# Controller-Sheet.net
KiCad netlist of a schematic drawn in Altium Designer
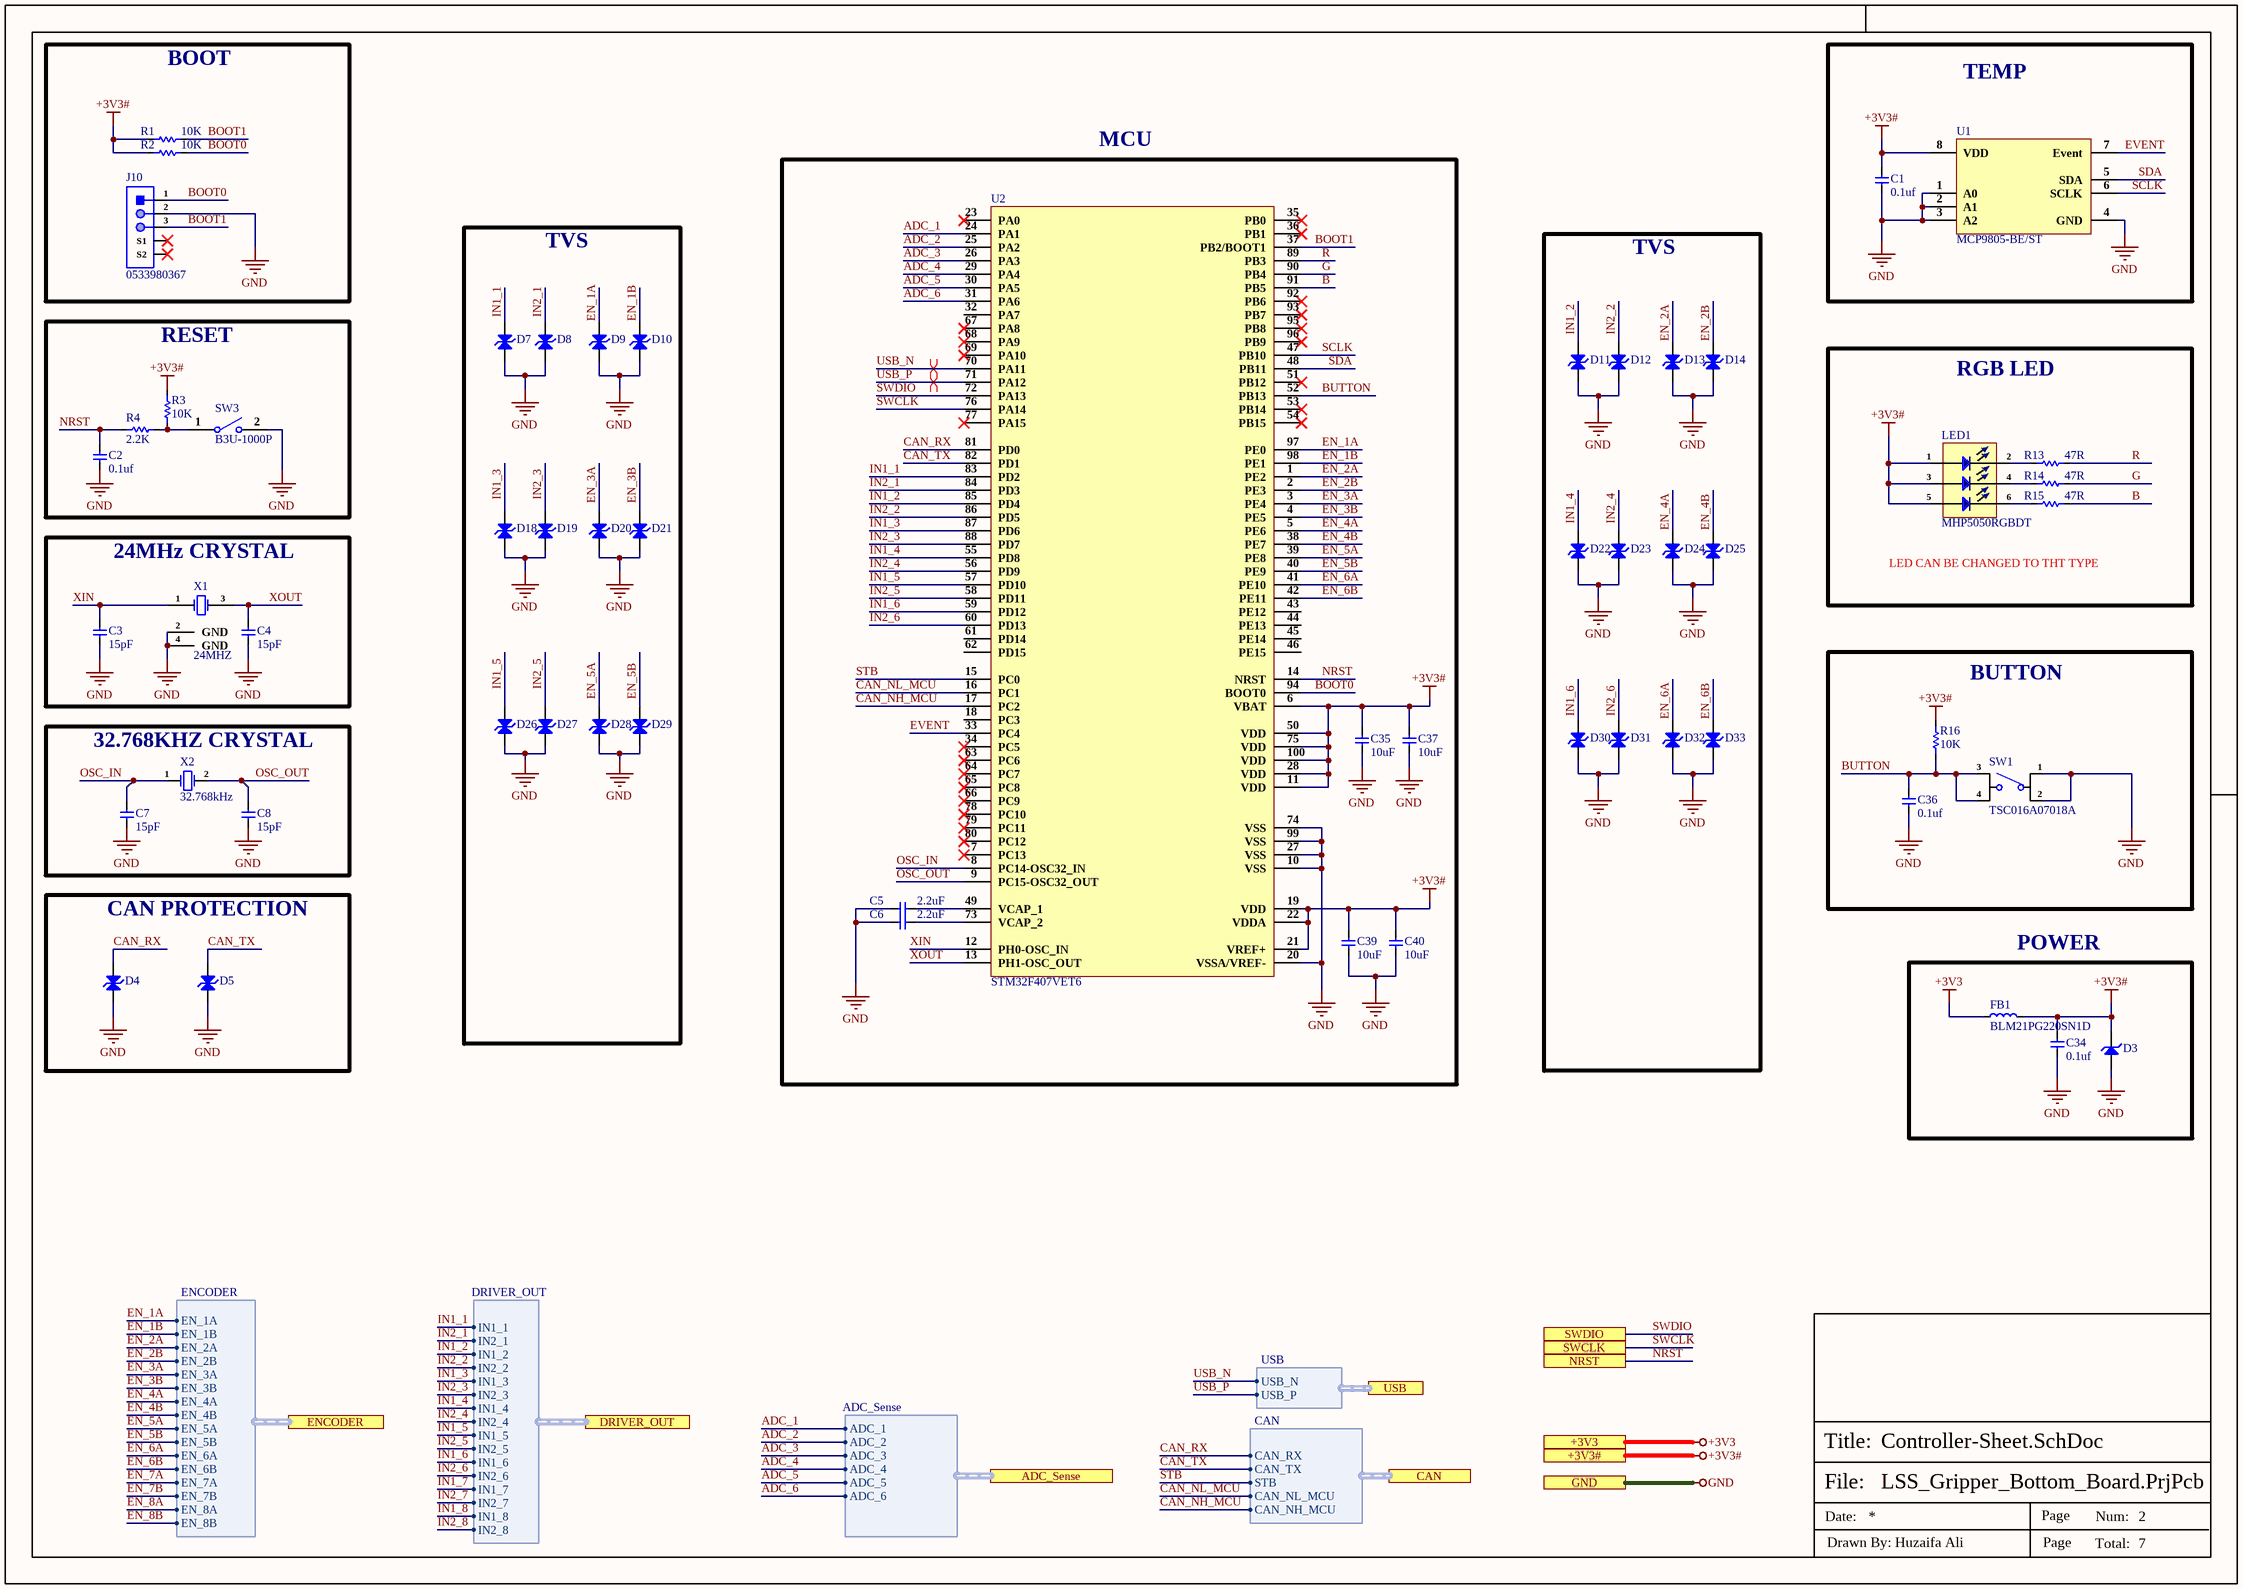
[diagram p0: Controller-Sheet.SchDoc]

(export (version "E")
  (design (tool "Eeschema 10.0.6"))
  (components
    (comp (ref "C1")
      (value "0.1uf")
      (footprint "Cap-0402")
      (description "CAP CER 0.1UF 100V X5R 0402")
      (fields
        (field (name "MANUFACTURER") "Murata")
        (field (name "MANUFACTURER PART NUMBER") "GRM155R62A104KE14D")
      )
      (libsource (lib "eSpark Libraries") (part "GRM155R62A104KE14D"))
    )
    (comp (ref "C2")
      (value "0.1uf")
      (footprint "Cap-0402")
      (description "CAP CER 0.1UF 100V X5R 0402")
      (fields
        (field (name "MANUFACTURER") "Murata")
        (field (name "MANUFACTURER PART NUMBER") "GRM155R62A104KE14D")
      )
      (libsource (lib "eSpark Libraries") (part "GRM155R62A104KE14D"))
    )
    (comp (ref "C3")
      (value "15pF")
      (footprint "Cap-0201")
      (description "CAP CER 15PF 50V C0G/NPO 0201")
      (fields
        (field (name "MANUFACTURER") "Yageo")
        (field (name "MANUFACTURER PART NUMBER") "CC0201JRNPO9BN150")
      )
      (libsource (lib "eSpark Libraries") (part "CC0201JRNPO9BN150"))
    )
    (comp (ref "C4")
      (value "15pF")
      (footprint "Cap-0201")
      (description "CAP CER 15PF 50V C0G/NPO 0201")
      (fields
        (field (name "MANUFACTURER") "Yageo")
        (field (name "MANUFACTURER PART NUMBER") "CC0201JRNPO9BN150")
      )
      (libsource (lib "eSpark Libraries") (part "CC0201JRNPO9BN150"))
    )
    (comp (ref "C5")
      (value "2.2uF")
      (footprint "Cap-0402")
      (description "CAP CER 2.2UF 6.3V X5R 0402")
      (fields
        (field (name "LCSC PART NUMBER") "C343036")
        (field (name "MANUFACTURER PART NUMBER") "C1005X5R0J225KTJA0E")
      )
      (libsource (lib "eSpark Libraries") (part "C1005X5R0J225KTJA0E"))
    )
    (comp (ref "C6")
      (value "2.2uF")
      (footprint "Cap-0402")
      (description "CAP CER 2.2UF 6.3V X5R 0402")
      (fields
        (field (name "LCSC PART NUMBER") "C343036")
        (field (name "MANUFACTURER PART NUMBER") "C1005X5R0J225KTJA0E")
      )
      (libsource (lib "eSpark Libraries") (part "C1005X5R0J225KTJA0E"))
    )
    (comp (ref "C7")
      (value "15pF")
      (footprint "Cap-0201")
      (description "CAP CER 15PF 50V C0G/NPO 0201")
      (fields
        (field (name "MANUFACTURER") "Yageo")
        (field (name "MANUFACTURER PART NUMBER") "CC0201JRNPO9BN150")
      )
      (libsource (lib "eSpark Libraries") (part "CC0201JRNPO9BN150"))
    )
    (comp (ref "C8")
      (value "15pF")
      (footprint "Cap-0201")
      (description "CAP CER 15PF 50V C0G/NPO 0201")
      (fields
        (field (name "MANUFACTURER") "Yageo")
        (field (name "MANUFACTURER PART NUMBER") "CC0201JRNPO9BN150")
      )
      (libsource (lib "eSpark Libraries") (part "CC0201JRNPO9BN150"))
    )
    (comp (ref "C34")
      (value "0.1uf")
      (footprint "Cap-0402")
      (description "CAP CER 0.1UF 100V X5R 0402")
      (fields
        (field (name "MANUFACTURER") "Murata")
        (field (name "MANUFACTURER PART NUMBER") "GRM155R62A104KE14D")
      )
      (libsource (lib "eSpark Libraries") (part "GRM155R62A104KE14D"))
    )
    (comp (ref "C35")
      (value "10uF")
      (footprint "Cap-0402")
      (description "CAP CER 10UF 10V X5R 0402")
      (fields
        (field (name "MANUFACTURER") "Samsung")
        (field (name "MANUFACTURER PART NUMBER") "CL05A106MP5NUNC")
      )
      (libsource (lib "eSpark Libraries") (part "CL05A106MP5NUNC"))
    )
    (comp (ref "C36")
      (value "0.1uf")
      (footprint "Cap-0402")
      (description "CAP CER 0.1UF 100V X5R 0402")
      (fields
        (field (name "MANUFACTURER") "Murata")
        (field (name "MANUFACTURER PART NUMBER") "GRM155R62A104KE14D")
      )
      (libsource (lib "eSpark Libraries") (part "GRM155R62A104KE14D"))
    )
    (comp (ref "C37")
      (value "10uF")
      (footprint "Cap-0402")
      (description "CAP CER 10UF 10V X5R 0402")
      (fields
        (field (name "MANUFACTURER") "Samsung")
        (field (name "MANUFACTURER PART NUMBER") "CL05A106MP5NUNC")
      )
      (libsource (lib "eSpark Libraries") (part "CL05A106MP5NUNC"))
    )
    (comp (ref "C39")
      (value "10uF")
      (footprint "Cap-0402")
      (description "CAP CER 10UF 10V X5R 0402")
      (fields
        (field (name "MANUFACTURER") "Samsung")
        (field (name "MANUFACTURER PART NUMBER") "CL05A106MP5NUNC")
      )
      (libsource (lib "eSpark Libraries") (part "CL05A106MP5NUNC"))
    )
    (comp (ref "C40")
      (value "10uF")
      (footprint "Cap-0402")
      (description "CAP CER 10UF 10V X5R 0402")
      (fields
        (field (name "MANUFACTURER") "Samsung")
        (field (name "MANUFACTURER PART NUMBER") "CL05A106MP5NUNC")
      )
      (libsource (lib "eSpark Libraries") (part "CL05A106MP5NUNC"))
    )
    (comp (ref "D3")
      (value "AZ3003-01G")
      (footprint "SOD-123")
      (description "TVS SURGE PROTECTOR 1-CH 3.3V")
      (fields (field (name "MANUFACTURER") "Amazing"))
      (libsource (lib "eSpark Libraries") (part "AZ3003-01G"))
    )
    (comp (ref "D4")
      (value "PESD3V3Y1BSFYL")
      (footprint "DSN0603-2")
      (description "TVS DIODE 3.3VWM 3.7VC DSN0603-2")
      (fields (field (name "MANUFACTURER") "Nexperia") (field (name "LCSC PART NUMBER") "C552535"))
      (libsource (lib "eSpark Libraries") (part "PESD3V3Y1BSFYL"))
    )
    (comp (ref "D5")
      (value "PESD3V3Y1BSFYL")
      (footprint "DSN0603-2")
      (description "TVS DIODE 3.3VWM 3.7VC DSN0603-2")
      (fields (field (name "MANUFACTURER") "Nexperia") (field (name "LCSC PART NUMBER") "C552535"))
      (libsource (lib "eSpark Libraries") (part "PESD3V3Y1BSFYL"))
    )
    (comp (ref "D7")
      (value "PESD3V3Y1BSFYL")
      (footprint "DSN0603-2")
      (description "TVS DIODE 3.3VWM 3.7VC DSN0603-2")
      (fields (field (name "MANUFACTURER") "Nexperia") (field (name "LCSC PART NUMBER") "C552535"))
      (libsource (lib "eSpark Libraries") (part "PESD3V3Y1BSFYL"))
    )
    (comp (ref "D8")
      (value "PESD3V3Y1BSFYL")
      (footprint "DSN0603-2")
      (description "TVS DIODE 3.3VWM 3.7VC DSN0603-2")
      (fields (field (name "MANUFACTURER") "Nexperia") (field (name "LCSC PART NUMBER") "C552535"))
      (libsource (lib "eSpark Libraries") (part "PESD3V3Y1BSFYL"))
    )
    (comp (ref "D9")
      (value "PESD3V3Y1BSFYL")
      (footprint "DSN0603-2")
      (description "TVS DIODE 3.3VWM 3.7VC DSN0603-2")
      (fields (field (name "MANUFACTURER") "Nexperia") (field (name "LCSC PART NUMBER") "C552535"))
      (libsource (lib "eSpark Libraries") (part "PESD3V3Y1BSFYL"))
    )
    (comp (ref "D10")
      (value "PESD3V3Y1BSFYL")
      (footprint "DSN0603-2")
      (description "TVS DIODE 3.3VWM 3.7VC DSN0603-2")
      (fields (field (name "MANUFACTURER") "Nexperia") (field (name "LCSC PART NUMBER") "C552535"))
      (libsource (lib "eSpark Libraries") (part "PESD3V3Y1BSFYL"))
    )
    (comp (ref "D11")
      (value "PESD3V3Y1BSFYL")
      (footprint "DSN0603-2")
      (description "TVS DIODE 3.3VWM 3.7VC DSN0603-2")
      (fields (field (name "MANUFACTURER") "Nexperia") (field (name "LCSC PART NUMBER") "C552535"))
      (libsource (lib "eSpark Libraries") (part "PESD3V3Y1BSFYL"))
    )
    (comp (ref "D12")
      (value "PESD3V3Y1BSFYL")
      (footprint "DSN0603-2")
      (description "TVS DIODE 3.3VWM 3.7VC DSN0603-2")
      (fields (field (name "MANUFACTURER") "Nexperia") (field (name "LCSC PART NUMBER") "C552535"))
      (libsource (lib "eSpark Libraries") (part "PESD3V3Y1BSFYL"))
    )
    (comp (ref "D13")
      (value "PESD3V3Y1BSFYL")
      (footprint "DSN0603-2")
      (description "TVS DIODE 3.3VWM 3.7VC DSN0603-2")
      (fields (field (name "MANUFACTURER") "Nexperia") (field (name "LCSC PART NUMBER") "C552535"))
      (libsource (lib "eSpark Libraries") (part "PESD3V3Y1BSFYL"))
    )
    (comp (ref "D14")
      (value "PESD3V3Y1BSFYL")
      (footprint "DSN0603-2")
      (description "TVS DIODE 3.3VWM 3.7VC DSN0603-2")
      (fields (field (name "MANUFACTURER") "Nexperia") (field (name "LCSC PART NUMBER") "C552535"))
      (libsource (lib "eSpark Libraries") (part "PESD3V3Y1BSFYL"))
    )
    (comp (ref "D18")
      (value "PESD3V3Y1BSFYL")
      (footprint "DSN0603-2")
      (description "TVS DIODE 3.3VWM 3.7VC DSN0603-2")
      (fields (field (name "MANUFACTURER") "Nexperia") (field (name "LCSC PART NUMBER") "C552535"))
      (libsource (lib "eSpark Libraries") (part "PESD3V3Y1BSFYL"))
    )
    (comp (ref "D19")
      (value "PESD3V3Y1BSFYL")
      (footprint "DSN0603-2")
      (description "TVS DIODE 3.3VWM 3.7VC DSN0603-2")
      (fields (field (name "MANUFACTURER") "Nexperia") (field (name "LCSC PART NUMBER") "C552535"))
      (libsource (lib "eSpark Libraries") (part "PESD3V3Y1BSFYL"))
    )
    (comp (ref "D20")
      (value "PESD3V3Y1BSFYL")
      (footprint "DSN0603-2")
      (description "TVS DIODE 3.3VWM 3.7VC DSN0603-2")
      (fields (field (name "MANUFACTURER") "Nexperia") (field (name "LCSC PART NUMBER") "C552535"))
      (libsource (lib "eSpark Libraries") (part "PESD3V3Y1BSFYL"))
    )
    (comp (ref "D21")
      (value "PESD3V3Y1BSFYL")
      (footprint "DSN0603-2")
      (description "TVS DIODE 3.3VWM 3.7VC DSN0603-2")
      (fields (field (name "MANUFACTURER") "Nexperia") (field (name "LCSC PART NUMBER") "C552535"))
      (libsource (lib "eSpark Libraries") (part "PESD3V3Y1BSFYL"))
    )
    (comp (ref "D22")
      (value "PESD3V3Y1BSFYL")
      (footprint "DSN0603-2")
      (description "TVS DIODE 3.3VWM 3.7VC DSN0603-2")
      (fields (field (name "MANUFACTURER") "Nexperia") (field (name "LCSC PART NUMBER") "C552535"))
      (libsource (lib "eSpark Libraries") (part "PESD3V3Y1BSFYL"))
    )
    (comp (ref "D23")
      (value "PESD3V3Y1BSFYL")
      (footprint "DSN0603-2")
      (description "TVS DIODE 3.3VWM 3.7VC DSN0603-2")
      (fields (field (name "MANUFACTURER") "Nexperia") (field (name "LCSC PART NUMBER") "C552535"))
      (libsource (lib "eSpark Libraries") (part "PESD3V3Y1BSFYL"))
    )
    (comp (ref "D24")
      (value "PESD3V3Y1BSFYL")
      (footprint "DSN0603-2")
      (description "TVS DIODE 3.3VWM 3.7VC DSN0603-2")
      (fields (field (name "MANUFACTURER") "Nexperia") (field (name "LCSC PART NUMBER") "C552535"))
      (libsource (lib "eSpark Libraries") (part "PESD3V3Y1BSFYL"))
    )
    (comp (ref "D25")
      (value "PESD3V3Y1BSFYL")
      (footprint "DSN0603-2")
      (description "TVS DIODE 3.3VWM 3.7VC DSN0603-2")
      (fields (field (name "MANUFACTURER") "Nexperia") (field (name "LCSC PART NUMBER") "C552535"))
      (libsource (lib "eSpark Libraries") (part "PESD3V3Y1BSFYL"))
    )
    (comp (ref "D26")
      (value "PESD3V3Y1BSFYL")
      (footprint "DSN0603-2")
      (description "TVS DIODE 3.3VWM 3.7VC DSN0603-2")
      (fields (field (name "MANUFACTURER") "Nexperia") (field (name "LCSC PART NUMBER") "C552535"))
      (libsource (lib "eSpark Libraries") (part "PESD3V3Y1BSFYL"))
    )
    (comp (ref "D27")
      (value "PESD3V3Y1BSFYL")
      (footprint "DSN0603-2")
      (description "TVS DIODE 3.3VWM 3.7VC DSN0603-2")
      (fields (field (name "MANUFACTURER") "Nexperia") (field (name "LCSC PART NUMBER") "C552535"))
      (libsource (lib "eSpark Libraries") (part "PESD3V3Y1BSFYL"))
    )
    (comp (ref "D28")
      (value "PESD3V3Y1BSFYL")
      (footprint "DSN0603-2")
      (description "TVS DIODE 3.3VWM 3.7VC DSN0603-2")
      (fields (field (name "MANUFACTURER") "Nexperia") (field (name "LCSC PART NUMBER") "C552535"))
      (libsource (lib "eSpark Libraries") (part "PESD3V3Y1BSFYL"))
    )
    (comp (ref "D29")
      (value "PESD3V3Y1BSFYL")
      (footprint "DSN0603-2")
      (description "TVS DIODE 3.3VWM 3.7VC DSN0603-2")
      (fields (field (name "MANUFACTURER") "Nexperia") (field (name "LCSC PART NUMBER") "C552535"))
      (libsource (lib "eSpark Libraries") (part "PESD3V3Y1BSFYL"))
    )
    (comp (ref "D30")
      (value "PESD3V3Y1BSFYL")
      (footprint "DSN0603-2")
      (description "TVS DIODE 3.3VWM 3.7VC DSN0603-2")
      (fields (field (name "MANUFACTURER") "Nexperia") (field (name "LCSC PART NUMBER") "C552535"))
      (libsource (lib "eSpark Libraries") (part "PESD3V3Y1BSFYL"))
    )
    (comp (ref "D31")
      (value "PESD3V3Y1BSFYL")
      (footprint "DSN0603-2")
      (description "TVS DIODE 3.3VWM 3.7VC DSN0603-2")
      (fields (field (name "MANUFACTURER") "Nexperia") (field (name "LCSC PART NUMBER") "C552535"))
      (libsource (lib "eSpark Libraries") (part "PESD3V3Y1BSFYL"))
    )
    (comp (ref "D32")
      (value "PESD3V3Y1BSFYL")
      (footprint "DSN0603-2")
      (description "TVS DIODE 3.3VWM 3.7VC DSN0603-2")
      (fields (field (name "MANUFACTURER") "Nexperia") (field (name "LCSC PART NUMBER") "C552535"))
      (libsource (lib "eSpark Libraries") (part "PESD3V3Y1BSFYL"))
    )
    (comp (ref "D33")
      (value "PESD3V3Y1BSFYL")
      (footprint "DSN0603-2")
      (description "TVS DIODE 3.3VWM 3.7VC DSN0603-2")
      (fields (field (name "MANUFACTURER") "Nexperia") (field (name "LCSC PART NUMBER") "C552535"))
      (libsource (lib "eSpark Libraries") (part "PESD3V3Y1BSFYL"))
    )
    (comp (ref "FB1")
      (value "BLM21PG220SN1D")
      (footprint "Ind-0805")
      (description "FERRITE BEAD 22 OHM 0805 1LN")
      (fields (field (name "MANUFACTURER") "Murata") (field (name "LCSC PART NUMBER") "C88993"))
      (libsource (lib "eSpark Libraries") (part "BLM21PG220SN1D"))
    )
    (comp (ref "J10")
      (value "0533980367")
      (footprint "0533980367")
      (description "CONN HEADER SMD 3POS 1.25MM")
      (fields (field (name "MANUFACTURER") "Molex") (field (name "LCSC PART NUMBER") "C17555262"))
      (libsource (lib "eSpark Libraries") (part "0533980367"))
    )
    (comp (ref "LED1")
      (value "MHP5050RGBDT")
      (footprint "SMD5050")
      (description "20mA White Diffused -40℃~+85℃ RGB SMD5050 Light Emitting Diodes (LED) ROHS")
      (fields (field (name "MANUFACTURER") "MEIHUA") (field (name "LCSC PART NUMBER") "C409780"))
      (libsource (lib "eSpark Libraries") (part "MHP5050RGBDT"))
    )
    (comp (ref "R1")
      (value "10K")
      (footprint "Res-0402")
      (description "RES 10K OHM 1% 1/16W 0402")
      (fields
        (field (name "MANUFACTURER") "Yageo")
        (field (name "MANUFACTURER PART NUMBER") "RC0402FR-0710KL")
      )
      (libsource (lib "eSpark Libraries") (part "RC0402FR-0710KL"))
    )
    (comp (ref "R2")
      (value "10K")
      (footprint "Res-0402")
      (description "RES 10K OHM 1% 1/16W 0402")
      (fields
        (field (name "MANUFACTURER") "Yageo")
        (field (name "MANUFACTURER PART NUMBER") "RC0402FR-0710KL")
      )
      (libsource (lib "eSpark Libraries") (part "RC0402FR-0710KL"))
    )
    (comp (ref "R3")
      (value "10K")
      (footprint "Res-0402")
      (description "RES 10K OHM 1% 1/16W 0402")
      (fields
        (field (name "MANUFACTURER") "Yageo")
        (field (name "MANUFACTURER PART NUMBER") "RC0402FR-0710KL")
      )
      (libsource (lib "eSpark Libraries") (part "RC0402FR-0710KL"))
    )
    (comp (ref "R4")
      (value "2.2K")
      (footprint "Res-0603")
      (description "RES SMD 2.2K OHM 0.1% 1/10W 0603")
      (fields
        (field (name "MANUFACTURER") "Yageo")
        (field (name "MANUFACTURER PART NUMBER") "RT0603BRB072K2L")
      )
      (libsource (lib "eSpark Libraries") (part "RT0603BRB072K2L"))
    )
    (comp (ref "R13")
      (value "47R")
      (footprint "Res-0402")
      (description "RES 47 OHM 1% 1/16W 0402")
      (fields
        (field (name "MANUFACTURER") "Yageo")
        (field (name "MANUFACTURER PART NUMBER") "RC0402FR-0747RL")
      )
      (libsource (lib "eSpark Libraries") (part "RC0402FR-0747RL"))
    )
    (comp (ref "R14")
      (value "47R")
      (footprint "Res-0402")
      (description "RES 47 OHM 1% 1/16W 0402")
      (fields
        (field (name "MANUFACTURER") "Yageo")
        (field (name "MANUFACTURER PART NUMBER") "RC0402FR-0747RL")
      )
      (libsource (lib "eSpark Libraries") (part "RC0402FR-0747RL"))
    )
    (comp (ref "R15")
      (value "47R")
      (footprint "Res-0402")
      (description "RES 47 OHM 1% 1/16W 0402")
      (fields
        (field (name "MANUFACTURER") "Yageo")
        (field (name "MANUFACTURER PART NUMBER") "RC0402FR-0747RL")
      )
      (libsource (lib "eSpark Libraries") (part "RC0402FR-0747RL"))
    )
    (comp (ref "R16")
      (value "10K")
      (footprint "Res-0402")
      (description "RES 10K OHM 1% 1/16W 0402")
      (fields
        (field (name "MANUFACTURER") "Yageo")
        (field (name "MANUFACTURER PART NUMBER") "RC0402FR-0710KL")
      )
      (libsource (lib "eSpark Libraries") (part "RC0402FR-0710KL"))
    )
    (comp (ref "SW1")
      (value "TSC016A07018A")
      (footprint "TSC016A07018A")
      (description "4.5mm 7mm 50mA Round Button Straight 4.5mm 180gf 12V Plugin Tactile Switches ROHS")
      (fields (field (name "MANUFACTURER") "BZCN") (field (name "LCSC PART NUMBER") "C2888497"))
      (libsource (lib "eSpark Libraries") (part "TSC016A07018A"))
    )
    (comp (ref "SW3")
      (value "B3U-1000P")
      (footprint "B3U-1000P")
      (description "SWITCH TACTILE SPST-NO 0.05A 12V")
      (fields (field (name "MANUFACTURER") "Omron") (field (name "LCSC PART NUMBER") "C231329"))
      (libsource (lib "eSpark Libraries") (part "B3U-1000P"))
    )
    (comp (ref "U1")
      (value "MCP9805-BE/ST")
      (footprint "8-TSSOP")
      (description "IC SENSOR THERMAL 3.0V 8TSSOP")
      (fields (field (name "MANUFACTURER") "Microchip") (field (name "LCSC PART NUMBER") "C636441"))
      (libsource (lib "eSpark Libraries") (part "MCP9805-BE/ST"))
    )
    (comp (ref "U2")
      (value "STM32F407VET6")
      (footprint "LQFP-100")
      (description "IC MCU 32BIT 512KB FLASH 100LQFP")
      (fields (field (name "MANUFACTURER") "STMicroelectronics") (field (name "LCSC PART NUMBER") "C28730"))
      (libsource (lib "eSpark Libraries") (part "STM32F407VET6"))
    )
    (comp (ref "X1")
      (value "24MHZ")
      (footprint "X322524MOB4SI-")
      (description "24MHz SMD Crystal Resonator 12pF ±10ppm ±30ppm -40℃~+85℃ SMD3225-4P Crystals ROHS")
      (fields
        (field (name "MANUFACTURER") "Yangxing Tech")
        (field (name "MANUFACTURER PART NUMBER") "X322524MOB4SI")
      )
      (libsource (lib "eSpark Libraries") (part "X322524MOB4SI"))
    )
    (comp (ref "X2")
      (value "32.768kHz")
      (footprint "SMD2012-2P")
      (description "CRYSTAL 32.7680KHZ 9PF SMD")
      (fields
        (field (name "MANUFACTURER") "Seiko Epson")
        (field (name "MANUFACTURER PART NUMBER") "FC-12M32.768KHZ7PF20PPM")
      )
      (libsource (lib "eSpark Libraries") (part "FC-12M32.768KHZ7PF20PPM"))
    )
  )
  (nets
    (net (code "6") (name "+3V3") (class "Default")
      (node (ref "FB1") (pin "1") (pinfunction "1_1") (pintype "passive"))
    )
    (net (code "7") (name "+3V3#") (class "Default")
      (node (ref "C1") (pin "2") (pinfunction "2_2") (pintype "passive"))
      (node (ref "C34") (pin "2") (pinfunction "2_2") (pintype "passive"))
      (node (ref "C35") (pin "2") (pinfunction "2_2") (pintype "passive"))
      (node (ref "C37") (pin "2") (pinfunction "2_2") (pintype "passive"))
      (node (ref "C39") (pin "2") (pinfunction "2_2") (pintype "passive"))
      (node (ref "C40") (pin "2") (pinfunction "2_2") (pintype "passive"))
      (node (ref "D3") (pin "2") (pinfunction "K_2") (pintype "passive"))
      (node (ref "FB1") (pin "2") (pinfunction "2_2") (pintype "passive"))
      (node (ref "LED1") (pin "1") (pinfunction "1_1") (pintype "passive"))
      (node (ref "LED1") (pin "3") (pinfunction "3_3") (pintype "passive"))
      (node (ref "LED1") (pin "5") (pinfunction "5_5") (pintype "passive"))
      (node (ref "R1") (pin "2") (pinfunction "2_2") (pintype "passive"))
      (node (ref "R16") (pin "1") (pinfunction "1_1") (pintype "passive"))
      (node (ref "R2") (pin "2") (pinfunction "2_2") (pintype "passive"))
      (node (ref "R3") (pin "1") (pinfunction "1_1") (pintype "passive"))
      (node (ref "U1") (pin "8") (pinfunction "VDD_8") (pintype "passive"))
      (node (ref "U2") (pin "100") (pinfunction "VDD_100") (pintype "passive"))
      (node (ref "U2") (pin "11") (pinfunction "VDD_11") (pintype "passive"))
      (node (ref "U2") (pin "19") (pinfunction "VDD_19") (pintype "passive"))
      (node (ref "U2") (pin "21") (pinfunction "VREF+_21") (pintype "passive"))
      (node (ref "U2") (pin "22") (pinfunction "VDDA_22") (pintype "passive"))
      (node (ref "U2") (pin "28") (pinfunction "VDD_28") (pintype "passive"))
      (node (ref "U2") (pin "50") (pinfunction "VDD_50") (pintype "passive"))
      (node (ref "U2") (pin "6") (pinfunction "VBAT_6") (pintype "passive"))
      (node (ref "U2") (pin "75") (pinfunction "VDD_75") (pintype "passive"))
    )
    (net (code "8") (name "/ADC_1") (class "Default")
      (node (ref "U2") (pin "24") (pinfunction "PA1_24") (pintype "passive"))
    )
    (net (code "9") (name "/ADC_2") (class "Default")
      (node (ref "U2") (pin "25") (pinfunction "PA2_25") (pintype "passive"))
    )
    (net (code "10") (name "/ADC_3") (class "Default")
      (node (ref "U2") (pin "26") (pinfunction "PA3_26") (pintype "passive"))
    )
    (net (code "11") (name "/ADC_4") (class "Default")
      (node (ref "U2") (pin "29") (pinfunction "PA4_29") (pintype "passive"))
    )
    (net (code "12") (name "/ADC_5") (class "Default")
      (node (ref "U2") (pin "30") (pinfunction "PA5_30") (pintype "passive"))
    )
    (net (code "13") (name "/ADC_6") (class "Default")
      (node (ref "U2") (pin "31") (pinfunction "PA6_31") (pintype "passive"))
    )
    (net (code "14") (name "/B") (class "Default")
      (node (ref "R15") (pin "2") (pinfunction "2_2") (pintype "passive"))
      (node (ref "U2") (pin "91") (pinfunction "PB5_91") (pintype "passive"))
    )
    (net (code "15") (name "/BOOT0") (class "Default")
      (node (ref "J10") (pin "1") (pinfunction "1_1") (pintype "passive"))
      (node (ref "R2") (pin "1") (pinfunction "1_1") (pintype "passive"))
      (node (ref "U2") (pin "94") (pinfunction "BOOT0_94") (pintype "passive"))
    )
    (net (code "16") (name "/BOOT1") (class "Default")
      (node (ref "J10") (pin "3") (pinfunction "3_3") (pintype "passive"))
      (node (ref "R1") (pin "1") (pinfunction "1_1") (pintype "passive"))
      (node (ref "U2") (pin "37") (pinfunction "PB2/BOOT1_37") (pintype "passive"))
    )
    (net (code "17") (name "/BUTTON") (class "Default")
      (node (ref "C36") (pin "2") (pinfunction "2_2") (pintype "passive"))
      (node (ref "R16") (pin "2") (pinfunction "2_2") (pintype "passive"))
      (node (ref "SW1") (pin "3") (pinfunction "3_3") (pintype "passive"))
      (node (ref "SW1") (pin "4") (pinfunction "4_4") (pintype "passive"))
      (node (ref "U2") (pin "52") (pinfunction "PB13_52") (pintype "passive"))
    )
    (net (code "18") (name "/CAN_NH_MCU") (class "Default")
      (node (ref "U2") (pin "17") (pinfunction "PC2_17") (pintype "passive"))
    )
    (net (code "19") (name "/CAN_NL_MCU") (class "Default")
      (node (ref "U2") (pin "16") (pinfunction "PC1_16") (pintype "passive"))
    )
    (net (code "20") (name "/CAN_RX") (class "Default")
      (node (ref "D4") (pin "2") (pinfunction "A_2") (pintype "passive"))
      (node (ref "U2") (pin "81") (pinfunction "PD0_81") (pintype "passive"))
    )
    (net (code "21") (name "/CAN_TX") (class "Default")
      (node (ref "D5") (pin "2") (pinfunction "A_2") (pintype "passive"))
      (node (ref "U2") (pin "82") (pinfunction "PD1_82") (pintype "passive"))
    )
    (net (code "22") (name "/EN_1A") (class "Default")
      (node (ref "D9") (pin "2") (pinfunction "A_2") (pintype "passive"))
      (node (ref "U2") (pin "97") (pinfunction "PE0_97") (pintype "passive"))
    )
    (net (code "23") (name "/EN_1B") (class "Default")
      (node (ref "D10") (pin "2") (pinfunction "A_2") (pintype "passive"))
      (node (ref "U2") (pin "98") (pinfunction "PE1_98") (pintype "passive"))
    )
    (net (code "24") (name "/EN_2A") (class "Default")
      (node (ref "D13") (pin "2") (pinfunction "A_2") (pintype "passive"))
      (node (ref "U2") (pin "1") (pinfunction "PE2_1") (pintype "passive"))
    )
    (net (code "25") (name "/EN_2B") (class "Default")
      (node (ref "D14") (pin "2") (pinfunction "A_2") (pintype "passive"))
      (node (ref "U2") (pin "2") (pinfunction "PE3_2") (pintype "passive"))
    )
    (net (code "26") (name "/EN_3A") (class "Default")
      (node (ref "D20") (pin "2") (pinfunction "A_2") (pintype "passive"))
      (node (ref "U2") (pin "3") (pinfunction "PE4_3") (pintype "passive"))
    )
    (net (code "27") (name "/EN_3B") (class "Default")
      (node (ref "D21") (pin "2") (pinfunction "A_2") (pintype "passive"))
      (node (ref "U2") (pin "4") (pinfunction "PE5_4") (pintype "passive"))
    )
    (net (code "28") (name "/EN_4A") (class "Default")
      (node (ref "D24") (pin "2") (pinfunction "A_2") (pintype "passive"))
      (node (ref "U2") (pin "5") (pinfunction "PE6_5") (pintype "passive"))
    )
    (net (code "29") (name "/EN_4B") (class "Default")
      (node (ref "D25") (pin "2") (pinfunction "A_2") (pintype "passive"))
      (node (ref "U2") (pin "38") (pinfunction "PE7_38") (pintype "passive"))
    )
    (net (code "30") (name "/EN_5A") (class "Default")
      (node (ref "D28") (pin "2") (pinfunction "A_2") (pintype "passive"))
      (node (ref "U2") (pin "39") (pinfunction "PE8_39") (pintype "passive"))
    )
    (net (code "31") (name "/EN_5B") (class "Default")
      (node (ref "D29") (pin "2") (pinfunction "A_2") (pintype "passive"))
      (node (ref "U2") (pin "40") (pinfunction "PE9_40") (pintype "passive"))
    )
    (net (code "32") (name "/EN_6A") (class "Default")
      (node (ref "D32") (pin "2") (pinfunction "A_2") (pintype "passive"))
      (node (ref "U2") (pin "41") (pinfunction "PE10_41") (pintype "passive"))
    )
    (net (code "33") (name "/EN_6B") (class "Default")
      (node (ref "D33") (pin "2") (pinfunction "A_2") (pintype "passive"))
      (node (ref "U2") (pin "42") (pinfunction "PE11_42") (pintype "passive"))
    )
    (net (code "38") (name "/EVENT") (class "Default")
      (node (ref "U1") (pin "7") (pinfunction "Event_7") (pintype "passive"))
      (node (ref "U2") (pin "33") (pinfunction "PC4_33") (pintype "passive"))
    )
    (net (code "39") (name "/G") (class "Default")
      (node (ref "R14") (pin "2") (pinfunction "2_2") (pintype "passive"))
      (node (ref "U2") (pin "90") (pinfunction "PB4_90") (pintype "passive"))
    )
    (net (code "40") (name "/IN1_1") (class "Default")
      (node (ref "D7") (pin "2") (pinfunction "A_2") (pintype "passive"))
      (node (ref "U2") (pin "83") (pinfunction "PD2_83") (pintype "passive"))
    )
    (net (code "41") (name "/IN1_2") (class "Default")
      (node (ref "D11") (pin "2") (pinfunction "A_2") (pintype "passive"))
      (node (ref "U2") (pin "85") (pinfunction "PD4_85") (pintype "passive"))
    )
    (net (code "42") (name "/IN1_3") (class "Default")
      (node (ref "D18") (pin "2") (pinfunction "A_2") (pintype "passive"))
      (node (ref "U2") (pin "87") (pinfunction "PD6_87") (pintype "passive"))
    )
    (net (code "43") (name "/IN1_4") (class "Default")
      (node (ref "D22") (pin "2") (pinfunction "A_2") (pintype "passive"))
      (node (ref "U2") (pin "55") (pinfunction "PD8_55") (pintype "passive"))
    )
    (net (code "44") (name "/IN1_5") (class "Default")
      (node (ref "D26") (pin "2") (pinfunction "A_2") (pintype "passive"))
      (node (ref "U2") (pin "57") (pinfunction "PD10_57") (pintype "passive"))
    )
    (net (code "45") (name "/IN1_6") (class "Default")
      (node (ref "D30") (pin "2") (pinfunction "A_2") (pintype "passive"))
      (node (ref "U2") (pin "59") (pinfunction "PD12_59") (pintype "passive"))
    )
    (net (code "48") (name "/IN2_1") (class "Default")
      (node (ref "D8") (pin "2") (pinfunction "A_2") (pintype "passive"))
      (node (ref "U2") (pin "84") (pinfunction "PD3_84") (pintype "passive"))
    )
    (net (code "49") (name "/IN2_2") (class "Default")
      (node (ref "D12") (pin "2") (pinfunction "A_2") (pintype "passive"))
      (node (ref "U2") (pin "86") (pinfunction "PD5_86") (pintype "passive"))
    )
    (net (code "50") (name "/IN2_3") (class "Default")
      (node (ref "D19") (pin "2") (pinfunction "A_2") (pintype "passive"))
      (node (ref "U2") (pin "88") (pinfunction "PD7_88") (pintype "passive"))
    )
    (net (code "51") (name "/IN2_4") (class "Default")
      (node (ref "D23") (pin "2") (pinfunction "A_2") (pintype "passive"))
      (node (ref "U2") (pin "56") (pinfunction "PD9_56") (pintype "passive"))
    )
    (net (code "52") (name "/IN2_5") (class "Default")
      (node (ref "D27") (pin "2") (pinfunction "A_2") (pintype "passive"))
      (node (ref "U2") (pin "58") (pinfunction "PD11_58") (pintype "passive"))
    )
    (net (code "53") (name "/IN2_6") (class "Default")
      (node (ref "D31") (pin "2") (pinfunction "A_2") (pintype "passive"))
      (node (ref "U2") (pin "60") (pinfunction "PD13_60") (pintype "passive"))
    )
    (net (code "56") (name "/NRST") (class "Default")
      (node (ref "C2") (pin "2") (pinfunction "2_2") (pintype "passive"))
      (node (ref "R4") (pin "1") (pinfunction "1_1") (pintype "passive"))
      (node (ref "U2") (pin "14") (pinfunction "NRST_14") (pintype "passive"))
    )
    (net (code "57") (name "/OSC_IN") (class "Default")
      (node (ref "C7") (pin "2") (pinfunction "2_2") (pintype "passive"))
      (node (ref "U2") (pin "8") (pinfunction "PC14-OSC32_IN_8") (pintype "passive"))
      (node (ref "X2") (pin "1") (pinfunction "OSC1_1") (pintype "passive"))
    )
    (net (code "58") (name "/OSC_OUT") (class "Default")
      (node (ref "C8") (pin "2") (pinfunction "2_2") (pintype "passive"))
      (node (ref "U2") (pin "9") (pinfunction "PC15-OSC32_OUT_9") (pintype "passive"))
      (node (ref "X2") (pin "2") (pinfunction "OSC2_2") (pintype "passive"))
    )
    (net (code "59") (name "/R") (class "Default")
      (node (ref "R13") (pin "2") (pinfunction "2_2") (pintype "passive"))
      (node (ref "U2") (pin "89") (pinfunction "PB3_89") (pintype "passive"))
    )
    (net (code "60") (name "/SCLK") (class "Default")
      (node (ref "U1") (pin "6") (pinfunction "SCLK_6") (pintype "passive"))
      (node (ref "U2") (pin "47") (pinfunction "PB10_47") (pintype "passive"))
    )
    (net (code "61") (name "/SDA") (class "Default")
      (node (ref "U1") (pin "5") (pinfunction "SDA_5") (pintype "passive"))
      (node (ref "U2") (pin "48") (pinfunction "PB11_48") (pintype "passive"))
    )
    (net (code "62") (name "/STB") (class "Default")
      (node (ref "U2") (pin "15") (pinfunction "PC0_15") (pintype "passive"))
    )
    (net (code "63") (name "/SWCLK") (class "Default")
      (node (ref "U2") (pin "76") (pinfunction "PA14_76") (pintype "passive"))
    )
    (net (code "64") (name "/SWDIO") (class "Default")
      (node (ref "U2") (pin "72") (pinfunction "PA13_72") (pintype "passive"))
    )
    (net (code "65") (name "/USB_N") (class "Default")
      (node (ref "U2") (pin "70") (pinfunction "PA11_70") (pintype "passive"))
    )
    (net (code "66") (name "/USB_P") (class "Default")
      (node (ref "U2") (pin "71") (pinfunction "PA12_71") (pintype "passive"))
    )
    (net (code "67") (name "/XIN") (class "Default")
      (node (ref "C3") (pin "2") (pinfunction "2_2") (pintype "passive"))
      (node (ref "U2") (pin "12") (pinfunction "PH0-OSC_IN_12") (pintype "passive"))
      (node (ref "X1") (pin "1") (pinfunction "CRYSTAL_1") (pintype "passive"))
    )
    (net (code "68") (name "/XOUT") (class "Default")
      (node (ref "C4") (pin "2") (pinfunction "2_2") (pintype "passive"))
      (node (ref "U2") (pin "13") (pinfunction "PH1-OSC_OUT_13") (pintype "passive"))
      (node (ref "X1") (pin "3") (pinfunction "CRYSTAL_3") (pintype "passive"))
    )
    (net (code "74") (name "GND") (class "Default")
      (node (ref "C1") (pin "1") (pinfunction "1_1") (pintype "passive"))
      (node (ref "C2") (pin "1") (pinfunction "1_1") (pintype "passive"))
      (node (ref "C3") (pin "1") (pinfunction "1_1") (pintype "passive"))
      (node (ref "C34") (pin "1") (pinfunction "1_1") (pintype "passive"))
      (node (ref "C35") (pin "1") (pinfunction "1_1") (pintype "passive"))
      (node (ref "C36") (pin "1") (pinfunction "1_1") (pintype "passive"))
      (node (ref "C37") (pin "1") (pinfunction "1_1") (pintype "passive"))
      (node (ref "C39") (pin "1") (pinfunction "1_1") (pintype "passive"))
      (node (ref "C4") (pin "1") (pinfunction "1_1") (pintype "passive"))
      (node (ref "C40") (pin "1") (pinfunction "1_1") (pintype "passive"))
      (node (ref "C5") (pin "1") (pinfunction "1_1") (pintype "passive"))
      (node (ref "C6") (pin "1") (pinfunction "1_1") (pintype "passive"))
      (node (ref "C7") (pin "1") (pinfunction "1_1") (pintype "passive"))
      (node (ref "C8") (pin "1") (pinfunction "1_1") (pintype "passive"))
      (node (ref "D10") (pin "1") (pinfunction "A_1") (pintype "passive"))
      (node (ref "D11") (pin "1") (pinfunction "A_1") (pintype "passive"))
      (node (ref "D12") (pin "1") (pinfunction "A_1") (pintype "passive"))
      (node (ref "D13") (pin "1") (pinfunction "A_1") (pintype "passive"))
      (node (ref "D14") (pin "1") (pinfunction "A_1") (pintype "passive"))
      (node (ref "D18") (pin "1") (pinfunction "A_1") (pintype "passive"))
      (node (ref "D19") (pin "1") (pinfunction "A_1") (pintype "passive"))
      (node (ref "D20") (pin "1") (pinfunction "A_1") (pintype "passive"))
      (node (ref "D21") (pin "1") (pinfunction "A_1") (pintype "passive"))
      (node (ref "D22") (pin "1") (pinfunction "A_1") (pintype "passive"))
      (node (ref "D23") (pin "1") (pinfunction "A_1") (pintype "passive"))
      (node (ref "D24") (pin "1") (pinfunction "A_1") (pintype "passive"))
      (node (ref "D25") (pin "1") (pinfunction "A_1") (pintype "passive"))
      (node (ref "D26") (pin "1") (pinfunction "A_1") (pintype "passive"))
      (node (ref "D27") (pin "1") (pinfunction "A_1") (pintype "passive"))
      (node (ref "D28") (pin "1") (pinfunction "A_1") (pintype "passive"))
      (node (ref "D29") (pin "1") (pinfunction "A_1") (pintype "passive"))
      (node (ref "D3") (pin "1") (pinfunction "A_1") (pintype "passive"))
      (node (ref "D30") (pin "1") (pinfunction "A_1") (pintype "passive"))
      (node (ref "D31") (pin "1") (pinfunction "A_1") (pintype "passive"))
      (node (ref "D32") (pin "1") (pinfunction "A_1") (pintype "passive"))
      (node (ref "D33") (pin "1") (pinfunction "A_1") (pintype "passive"))
      (node (ref "D4") (pin "1") (pinfunction "A_1") (pintype "passive"))
      (node (ref "D5") (pin "1") (pinfunction "A_1") (pintype "passive"))
      (node (ref "D7") (pin "1") (pinfunction "A_1") (pintype "passive"))
      (node (ref "D8") (pin "1") (pinfunction "A_1") (pintype "passive"))
      (node (ref "D9") (pin "1") (pinfunction "A_1") (pintype "passive"))
      (node (ref "J10") (pin "2") (pinfunction "2_2") (pintype "passive"))
      (node (ref "SW1") (pin "1") (pinfunction "1_1") (pintype "passive"))
      (node (ref "SW1") (pin "2") (pinfunction "2_2") (pintype "passive"))
      (node (ref "SW3") (pin "2") (pinfunction "2_2") (pintype "passive"))
      (node (ref "U1") (pin "1") (pinfunction "A0_1") (pintype "passive"))
      (node (ref "U1") (pin "2") (pinfunction "A1_2") (pintype "passive"))
      (node (ref "U1") (pin "3") (pinfunction "A2_3") (pintype "passive"))
      (node (ref "U1") (pin "4") (pinfunction "GND_4") (pintype "passive"))
      (node (ref "U2") (pin "10") (pinfunction "VSS_10") (pintype "passive"))
      (node (ref "U2") (pin "20") (pinfunction "VSSA/VREF-_20") (pintype "passive"))
      (node (ref "U2") (pin "27") (pinfunction "VSS_27") (pintype "passive"))
      (node (ref "U2") (pin "74") (pinfunction "VSS_74") (pintype "passive"))
      (node (ref "U2") (pin "99") (pinfunction "VSS_99") (pintype "passive"))
      (node (ref "X1") (pin "2") (pinfunction "GND_2") (pintype "passive"))
      (node (ref "X1") (pin "4") (pinfunction "GND_4") (pintype "passive"))
    )
    (net (code "75") (name "Net-(LED1-Pad2)") (class "Default")
      (node (ref "LED1") (pin "2") (pinfunction "2_2") (pintype "passive"))
      (node (ref "R13") (pin "1") (pinfunction "1_1") (pintype "passive"))
    )
    (net (code "76") (name "Net-(LED1-Pad4)") (class "Default")
      (node (ref "LED1") (pin "4") (pinfunction "4_4") (pintype "passive"))
      (node (ref "R14") (pin "1") (pinfunction "1_1") (pintype "passive"))
    )
    (net (code "77") (name "Net-(LED1-Pad6)") (class "Default")
      (node (ref "LED1") (pin "6") (pinfunction "6_6") (pintype "passive"))
      (node (ref "R15") (pin "1") (pinfunction "1_1") (pintype "passive"))
    )
    (net (code "78") (name "Net-(R3-Pad2)") (class "Default")
      (node (ref "R3") (pin "2") (pinfunction "2_2") (pintype "passive"))
      (node (ref "R4") (pin "2") (pinfunction "2_2") (pintype "passive"))
      (node (ref "SW3") (pin "1") (pinfunction "1_1") (pintype "passive"))
    )
    (net (code "79") (name "Net-(U2-VCAP_1)") (class "Default")
      (node (ref "C5") (pin "2") (pinfunction "2_2") (pintype "passive"))
      (node (ref "U2") (pin "49") (pinfunction "VCAP_1_49") (pintype "passive"))
    )
    (net (code "80") (name "Net-(U2-VCAP_2)") (class "Default")
      (node (ref "C6") (pin "2") (pinfunction "2_2") (pintype "passive"))
      (node (ref "U2") (pin "73") (pinfunction "VCAP_2_73") (pintype "passive"))
    )
    (net (code "81") (name "unconnected-(J10-PadS1)") (class "Default")
      (node (ref "J10") (pin "S1") (pinfunction "S1_S1") (pintype "passive+no_connect"))
    )
    (net (code "82") (name "unconnected-(J10-PadS2)") (class "Default")
      (node (ref "J10") (pin "S2") (pinfunction "S2_S2") (pintype "passive+no_connect"))
    )
    (net (code "83") (name "unconnected-(U2-PA0-Pad23)") (class "Default")
      (node (ref "U2") (pin "23") (pinfunction "PA0_23") (pintype "passive+no_connect"))
    )
    (net (code "84") (name "unconnected-(U2-PA7-Pad32)") (class "Default")
      (node (ref "U2") (pin "32") (pinfunction "PA7_32") (pintype "passive"))
    )
    (net (code "85") (name "unconnected-(U2-PA8-Pad67)") (class "Default")
      (node (ref "U2") (pin "67") (pinfunction "PA8_67") (pintype "passive+no_connect"))
    )
    (net (code "86") (name "unconnected-(U2-PA9-Pad68)") (class "Default")
      (node (ref "U2") (pin "68") (pinfunction "PA9_68") (pintype "passive+no_connect"))
    )
    (net (code "87") (name "unconnected-(U2-PA10-Pad69)") (class "Default")
      (node (ref "U2") (pin "69") (pinfunction "PA10_69") (pintype "passive+no_connect"))
    )
    (net (code "88") (name "unconnected-(U2-PA15-Pad77)") (class "Default")
      (node (ref "U2") (pin "77") (pinfunction "PA15_77") (pintype "passive+no_connect"))
    )
    (net (code "89") (name "unconnected-(U2-PB0-Pad35)") (class "Default")
      (node (ref "U2") (pin "35") (pinfunction "PB0_35") (pintype "passive+no_connect"))
    )
    (net (code "90") (name "unconnected-(U2-PB1-Pad36)") (class "Default")
      (node (ref "U2") (pin "36") (pinfunction "PB1_36") (pintype "passive+no_connect"))
    )
    (net (code "91") (name "unconnected-(U2-PB6-Pad92)") (class "Default")
      (node (ref "U2") (pin "92") (pinfunction "PB6_92") (pintype "passive+no_connect"))
    )
    (net (code "92") (name "unconnected-(U2-PB7-Pad93)") (class "Default")
      (node (ref "U2") (pin "93") (pinfunction "PB7_93") (pintype "passive+no_connect"))
    )
    (net (code "93") (name "unconnected-(U2-PB8-Pad95)") (class "Default")
      (node (ref "U2") (pin "95") (pinfunction "PB8_95") (pintype "passive+no_connect"))
    )
    (net (code "94") (name "unconnected-(U2-PB9-Pad96)") (class "Default")
      (node (ref "U2") (pin "96") (pinfunction "PB9_96") (pintype "passive+no_connect"))
    )
    (net (code "95") (name "unconnected-(U2-PB12-Pad51)") (class "Default")
      (node (ref "U2") (pin "51") (pinfunction "PB12_51") (pintype "passive+no_connect"))
    )
    (net (code "96") (name "unconnected-(U2-PB14-Pad53)") (class "Default")
      (node (ref "U2") (pin "53") (pinfunction "PB14_53") (pintype "passive+no_connect"))
    )
    (net (code "97") (name "unconnected-(U2-PB15-Pad54)") (class "Default")
      (node (ref "U2") (pin "54") (pinfunction "PB15_54") (pintype "passive+no_connect"))
    )
    (net (code "98") (name "unconnected-(U2-PC3-Pad18)") (class "Default")
      (node (ref "U2") (pin "18") (pinfunction "PC3_18") (pintype "passive"))
    )
    (net (code "99") (name "unconnected-(U2-PC5-Pad34)") (class "Default")
      (node (ref "U2") (pin "34") (pinfunction "PC5_34") (pintype "passive+no_connect"))
    )
    (net (code "100") (name "unconnected-(U2-PC6-Pad63)") (class "Default")
      (node (ref "U2") (pin "63") (pinfunction "PC6_63") (pintype "passive+no_connect"))
    )
    (net (code "101") (name "unconnected-(U2-PC7-Pad64)") (class "Default")
      (node (ref "U2") (pin "64") (pinfunction "PC7_64") (pintype "passive+no_connect"))
    )
    (net (code "102") (name "unconnected-(U2-PC8-Pad65)") (class "Default")
      (node (ref "U2") (pin "65") (pinfunction "PC8_65") (pintype "passive+no_connect"))
    )
    (net (code "103") (name "unconnected-(U2-PC9-Pad66)") (class "Default")
      (node (ref "U2") (pin "66") (pinfunction "PC9_66") (pintype "passive+no_connect"))
    )
    (net (code "104") (name "unconnected-(U2-PC10-Pad78)") (class "Default")
      (node (ref "U2") (pin "78") (pinfunction "PC10_78") (pintype "passive+no_connect"))
    )
    (net (code "105") (name "unconnected-(U2-PC11-Pad79)") (class "Default")
      (node (ref "U2") (pin "79") (pinfunction "PC11_79") (pintype "passive+no_connect"))
    )
    (net (code "106") (name "unconnected-(U2-PC12-Pad80)") (class "Default")
      (node (ref "U2") (pin "80") (pinfunction "PC12_80") (pintype "passive+no_connect"))
    )
    (net (code "107") (name "unconnected-(U2-PC13-Pad7)") (class "Default")
      (node (ref "U2") (pin "7") (pinfunction "PC13_7") (pintype "passive+no_connect"))
    )
    (net (code "108") (name "unconnected-(U2-PD14-Pad61)") (class "Default")
      (node (ref "U2") (pin "61") (pinfunction "PD14_61") (pintype "passive"))
    )
    (net (code "109") (name "unconnected-(U2-PD15-Pad62)") (class "Default")
      (node (ref "U2") (pin "62") (pinfunction "PD15_62") (pintype "passive"))
    )
    (net (code "110") (name "unconnected-(U2-PE12-Pad43)") (class "Default")
      (node (ref "U2") (pin "43") (pinfunction "PE12_43") (pintype "passive"))
    )
    (net (code "111") (name "unconnected-(U2-PE13-Pad44)") (class "Default")
      (node (ref "U2") (pin "44") (pinfunction "PE13_44") (pintype "passive"))
    )
    (net (code "112") (name "unconnected-(U2-PE14-Pad45)") (class "Default")
      (node (ref "U2") (pin "45") (pinfunction "PE14_45") (pintype "passive"))
    )
    (net (code "113") (name "unconnected-(U2-PE15-Pad46)") (class "Default")
      (node (ref "U2") (pin "46") (pinfunction "PE15_46") (pintype "passive"))
    )
  )
)
